# sensor.net
KiCad netlist of a schematic drawn in Altium Designer
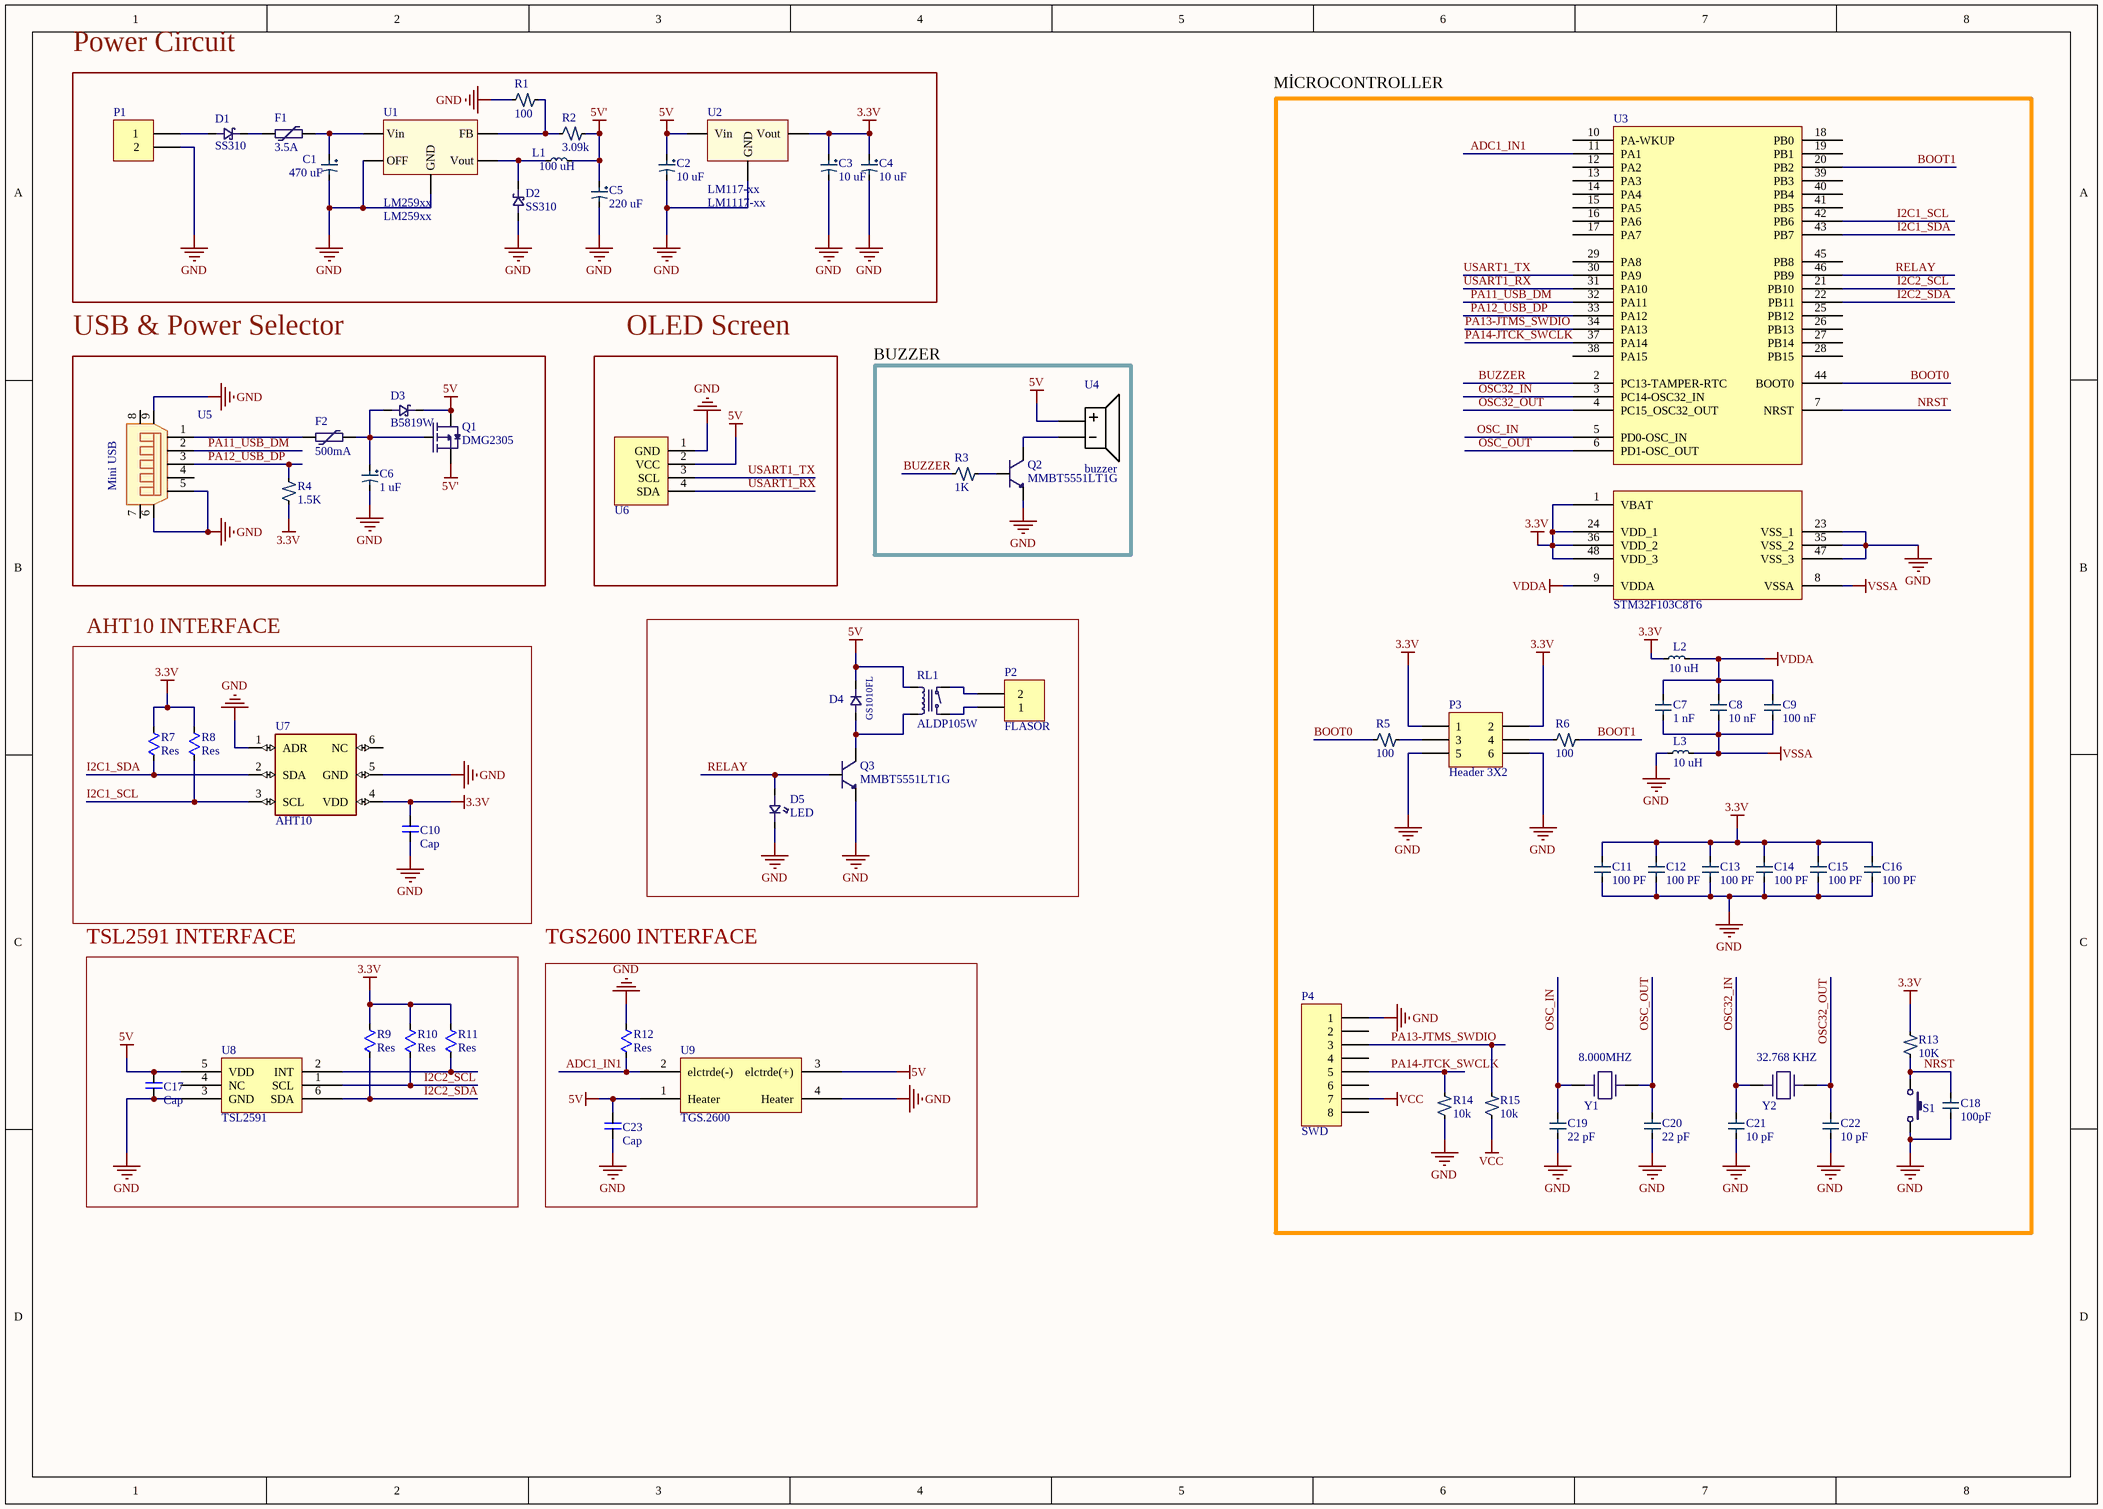
[diagram p0: sensor.SchDoc]

(export (version "E")
  (design (tool "Eeschema 10.0.6"))
  (components
    (comp (ref "C1")
      (value "470 uF")
      (footprint "10X10.5 Cap")
      (description "Cap Pole")
      (libsource (lib "Passive Comp") (part "Capasitor Pole"))
    )
    (comp (ref "C2")
      (value "10 uF")
      (footprint "Case A")
      (description "Cap Pole")
      (libsource (lib "Passive Comp") (part "Capasitor Pole"))
    )
    (comp (ref "C3")
      (value "10 uF")
      (footprint "Case A")
      (description "Cap Pole")
      (libsource (lib "Passive Comp") (part "Capasitor Pole"))
    )
    (comp (ref "C4")
      (value "10 uF")
      (footprint "Case A")
      (description "Cap Pole")
      (libsource (lib "Passive Comp") (part "Capasitor Pole"))
    )
    (comp (ref "C5")
      (value "220 uF")
      (footprint "10X10.5 Cap")
      (description "Cap Pole")
      (libsource (lib "Passive Comp") (part "Capasitor Pole"))
    )
    (comp (ref "C6")
      (value "1 uF")
      (footprint "Case A")
      (description "Cap Pole")
      (libsource (lib "Passive Comp") (part "Capasitor Pole"))
    )
    (comp (ref "C7")
      (value "1 nF")
      (footprint "0603 CAP")
      (description "Cap SMD")
      (libsource (lib "Passive Comp") (part "Capasitor"))
    )
    (comp (ref "C8")
      (value "10 nF")
      (footprint "0603 CAP")
      (description "Cap SMD")
      (libsource (lib "Passive Comp") (part "Capasitor"))
    )
    (comp (ref "C9")
      (value "100 nF")
      (footprint "0603 CAP")
      (description "Cap SMD")
      (libsource (lib "Passive Comp") (part "Capasitor"))
    )
    (comp (ref "C10")
      (value "Cap")
      (footprint "0805 Cap")
      (description "Cap Small")
      (libsource (lib "Passive Comp.") (part "Cap"))
    )
    (comp (ref "C11")
      (value "100 PF")
      (footprint "0603 CAP")
      (description "Cap SMD")
      (libsource (lib "Passive Comp") (part "Capasitor"))
    )
    (comp (ref "C12")
      (value "100 PF")
      (footprint "0603 CAP")
      (description "Cap SMD")
      (libsource (lib "Passive Comp") (part "Capasitor"))
    )
    (comp (ref "C13")
      (value "100 PF")
      (footprint "0603 CAP")
      (description "Cap SMD")
      (libsource (lib "Passive Comp") (part "Capasitor"))
    )
    (comp (ref "C14")
      (value "100 PF")
      (footprint "0603 CAP")
      (description "Cap SMD")
      (libsource (lib "Passive Comp") (part "Capasitor"))
    )
    (comp (ref "C15")
      (value "100 PF")
      (footprint "0603 CAP")
      (description "Cap SMD")
      (libsource (lib "Passive Comp") (part "Capasitor"))
    )
    (comp (ref "C16")
      (value "100 PF")
      (footprint "0603 CAP")
      (description "Cap SMD")
      (libsource (lib "Passive Comp") (part "Capasitor"))
    )
    (comp (ref "C17")
      (value "Cap")
      (footprint "0603 CAP")
      (description "Cap Small")
      (libsource (lib "Passive Comp.") (part "Cap"))
    )
    (comp (ref "C18")
      (value "100pF")
      (footprint "0603 CAP")
      (description "Cap SMD")
      (libsource (lib "Passive Comp") (part "Capasitor"))
    )
    (comp (ref "C19")
      (value "22 pF")
      (footprint "0603 CAP")
      (description "Cap SMD")
      (libsource (lib "Passive Comp") (part "Capasitor"))
    )
    (comp (ref "C20")
      (value "22 pF")
      (footprint "0603 CAP")
      (description "Cap SMD")
      (libsource (lib "Passive Comp") (part "Capasitor"))
    )
    (comp (ref "C21")
      (value "10 pF")
      (footprint "0603 CAP")
      (description "Cap SMD")
      (libsource (lib "Passive Comp") (part "Capasitor"))
    )
    (comp (ref "C22")
      (value "10 pF")
      (footprint "0603 CAP")
      (description "Cap SMD")
      (libsource (lib "Passive Comp") (part "Capasitor"))
    )
    (comp (ref "C23")
      (value "Cap")
      (footprint "0603 CAP")
      (description "Cap Small")
      (libsource (lib "Passive Comp.") (part "Cap"))
    )
    (comp (ref "D1")
      (value "SS310")
      (footprint "DO-214AA")
      (description "DIODE SCHOTTKY 3A 100V DO-214AA SMB HOTTECH")
      (libsource (lib "Diyot") (part "SS310-DO214AA-HT"))
    )
    (comp (ref "D2")
      (value "SS310")
      (footprint "DO-214AA")
      (description "DIODE SCHOTTKY 3A 100V DO-214AA SMB HOTTECH")
      (libsource (lib "Diyot") (part "SS310-DO214AA-HT"))
    )
    (comp (ref "D3")
      (value "B5819W")
      (footprint "SOD123")
      (description "DIODE SCHOTTKY 1A 40V SOD123")
      (libsource (lib "Diyot") (part "B5819W"))
    )
    (comp (ref "D4")
      (value "GS1010FL")
      (footprint "SOD123FL")
      (description "DIODE STAND. Single 1A 1000V SMT SOD123FL")
      (libsource (lib "Diyot") (part "GS1010FL_R1_00001"))
    )
    (comp (ref "D5") (value "LED") (footprint "0603 Led") (libsource (lib "Diyot") (part "LED")))
    (comp (ref "F1")
      (value "3.5A")
      (footprint "6125 Fuse")
      (description "25H0500G 125V 500mA 6125 SMD Sigorta")
      (libsource (lib "Fuse") (part "SMD Fuse"))
    )
    (comp (ref "F2")
      (value "500mA")
      (footprint "6125 Fuse")
      (description "25H0500G 125V 500mA 6125 SMD Sigorta")
      (libsource (lib "Fuse") (part "SMD Fuse"))
    )
    (comp (ref "L1")
      (value "100 uH")
      (footprint "12X12X5MM INDUCTOR")
      (description "IND SMD")
      (libsource (lib "Passive Comp") (part "Inductor"))
    )
    (comp (ref "L2")
      (value "10 uH")
      (footprint "0603 IND")
      (description "IND SMD")
      (libsource (lib "Passive Comp") (part "Inductor"))
    )
    (comp (ref "L3")
      (value "10 uH")
      (footprint "0603 IND")
      (description "IND SMD")
      (libsource (lib "Passive Comp") (part "Inductor"))
    )
    (comp (ref "P1")
      (value "Klemens 5.08")
      (footprint "KLEMENS 5.08MM-2")
      (description "2 Pin 5.08mm 90° Erkek Geçmeli Turuncu Klemens")
      (libsource (lib "Klemens") (part "Klemens 5.08 2 pin"))
    )
    (comp (ref "P2")
      (value "FLASÖR")
      (footprint "KLEMENS 5.08MM-2")
      (description "2 Pin 5.08mm 90° Erkek Geçmeli Turuncu Klemens")
      (libsource (lib "") (part "Klemens 5.08 2 pin_1"))
    )
    (comp (ref "P3")
      (value "Header 3X2")
      (footprint "HDR2X3")
      (description "Header, 3-Pin, Dual row")
      (fields (field (name "PUBLISHER") "Altium Limited"))
      (libsource (lib "Miscellaneous Connectors") (part "Header 3X2"))
    )
    (comp (ref "P4")
      (value "SWD")
      (footprint "2X4 BOX HEADER")
      (description "FEMALE HEADER 2X4 90C")
      (libsource (lib "Header") (part "FEMALE HEADER 2X4 90C"))
    )
    (comp (ref "Q1")
      (value "DMG2305")
      (footprint "SOT23")
      (description "MOSFET DIS.4.2A 20V P-CH SOT23 ENHANCEMENT SMT")
      (libsource (lib "Anahtarlama") (part "DMG2305"))
    )
    (comp (ref "Q2")
      (value "MMBT5551LT1G")
      (footprint "SOT23")
      (description "TRANSISTOR DIS.600mA 160V NPN SOT23 H.VOLT SMT")
      (libsource (lib "Anahtarlama") (part "MMBT5551LT1G"))
    )
    (comp (ref "Q3")
      (value "MMBT5551LT1G")
      (footprint "SOT23")
      (description "TRANSISTOR DIS.600mA 160V NPN SOT23 H.VOLT SMT")
      (libsource (lib "Anahtarlama") (part "MMBT5551LT1G"))
    )
    (comp (ref "R1")
      (value "100")
      (footprint "0603 RES")
      (description "Res SMD")
      (libsource (lib "Passive Comp") (part "Resistor"))
    )
    (comp (ref "R2")
      (value "3.09k")
      (footprint "0603 RES")
      (description "Res SMD")
      (libsource (lib "Passive Comp") (part "Resistor"))
    )
    (comp (ref "R3")
      (value "1K")
      (footprint "0603 RES")
      (description "Res SMD")
      (libsource (lib "") (part "Resistor_1"))
    )
    (comp (ref "R4")
      (value "1.5K")
      (footprint "0603 RES")
      (description "Res SMD")
      (libsource (lib "Passive Comp") (part "Resistor"))
    )
    (comp (ref "R5")
      (value "100")
      (footprint "0603 RES")
      (description "Res SMD")
      (libsource (lib "Passive Comp") (part "Resistor"))
    )
    (comp (ref "R6")
      (value "100")
      (footprint "0603 RES")
      (description "Res SMD")
      (libsource (lib "Passive Comp") (part "Resistor"))
    )
    (comp (ref "R7")
      (value "Res")
      (footprint "0603 RES")
      (description "Res Small")
      (libsource (lib "Passive Comp.") (part "Res"))
    )
    (comp (ref "R8")
      (value "Res")
      (footprint "0603 RES")
      (description "Res Small")
      (libsource (lib "Passive Comp.") (part "Res"))
    )
    (comp (ref "R9")
      (value "Res")
      (footprint "0603 RES")
      (description "Res Small")
      (libsource (lib "Passive Comp.") (part "Res"))
    )
    (comp (ref "R10")
      (value "Res")
      (footprint "0603 RES")
      (description "Res Small")
      (libsource (lib "Passive Comp.") (part "Res"))
    )
    (comp (ref "R11")
      (value "Res")
      (footprint "0603 RES")
      (description "Res Small")
      (libsource (lib "Passive Comp.") (part "Res"))
    )
    (comp (ref "R12")
      (value "Res")
      (footprint "0603 RES")
      (description "Res Small")
      (libsource (lib "Passive Comp.") (part "Res"))
    )
    (comp (ref "R13")
      (value "10K")
      (footprint "0603 RES")
      (description "Res SMD")
      (libsource (lib "Passive Comp") (part "Resistor"))
    )
    (comp (ref "R14")
      (value "10k")
      (footprint "0603 RES")
      (description "Res SMD")
      (libsource (lib "Passive Comp") (part "Resistor"))
    )
    (comp (ref "R15")
      (value "10k")
      (footprint "0603 RES")
      (description "Res SMD")
      (libsource (lib "Passive Comp") (part "Resistor"))
    )
    (comp (ref "RL1")
      (value "ALDP105W")
      (footprint "SPST-NO (1 Form A)")
      (description "RELAY 5A 5V 1a PANASONIC")
      (libsource (lib "Anahtarlama") (part "ALDP105W"))
    )
    (comp (ref "S1")
      (value "Switch")
      (footprint "6x6mm Tach Switch")
      (description "SWITCH TACT 6.00x6.00 4.30mm 250gF SMT V/T")
      (libsource (lib "Switch") (part "Switch Tach V/T"))
    )
    (comp (ref "U1")
      (value "LM259xx")
      (footprint "d2pak-5")
      (description "Voltaga Regulator")
      (fields (field (name "ALTIUM_VALUE") "LM259xx"))
      (libsource (lib "Voltage Reg.") (part "LM259xx"))
    )
    (comp (ref "U2")
      (value "LM117-xx")
      (footprint "SOT223-3")
      (description "Voltaga Regulator")
      (fields (field (name "ALTIUM_VALUE") "LM1117-xx"))
      (libsource (lib "Voltage Reg.") (part "LM117-xx"))
    )
    (comp (ref "U3")
      (value "STM32F103C8T6")
      (footprint "LQFP48")
      (description "IC-32F103C MCU 32BIT 64KB FLASH 48LQFP")
      (libsource (lib "STM") (part "STM32F103C8T6TR"))
    )
    (comp (ref "U4") (value "buzzer") (footprint "BUZZER") (libsource (lib "buzzer") (part "buzzer")))
    (comp (ref "U5")
      (value "Mini USB")
      (footprint "MİNİ USB")
      (description "CONNECTORUSB MINI B TYPE 5PIN SMT R/A FEMALE")
      (libsource (lib "Usb") (part "Mini USB"))
    )
    (comp (ref "U6")
      (value "OLED 128X32")
      (footprint "128x32 OLED")
      (description "128x32 Oled Lcd Ekran 0.91 Inch SSD1306")
      (libsource (lib "Ekran") (part "OLED 128X32"))
    )
    (comp (ref "U7")
      (value "AHT10")
      (footprint "AHT_QFN")
      (description "Temperature and humidity sensor")
      (fields (field (name "MF") "Asair"))
      (libsource (lib "AHT10") (part "AHT10"))
    )
    (comp (ref "U8")
      (value "TSL2591")
      (footprint "SON65P200X200X90-7N")
      (libsource (lib "TSL2591") (part "TSL2591"))
    )
    (comp (ref "U9")
      (value "TGS.2600")
      (footprint "TO180P920H1340-4")
      (libsource (lib "TGS2600") (part "TGS.2600"))
    )
    (comp (ref "Y1")
      (value "8.000MHZ")
      (footprint "SMD-2 XTAL")
      (description "CRYSTAL 8MHZ 18PF 2-SMD ABRACON")
      (libsource (lib "XTAL") (part "8 MHZ XTAL"))
    )
    (comp (ref "Y2")
      (value "32.768 KHZ")
      (footprint "3.20x1.50x0.80")
      (description "CRYSTAL 32.7680kHz 12.5pF 20ppm")
      (libsource (lib "XTAL") (part "32.7680kHz"))
    )
  )
  (nets
    (net (code "2") (name "/ADC1_IN1") (class "Default")
      (node (ref "R12") (pin "1") (pinfunction "1_1") (pintype "passive"))
      (node (ref "U3") (pin "11") (pinfunction "PA1_11") (pintype "passive"))
      (node (ref "U9") (pin "2") (pinfunction "elctrde(-)_2") (pintype "passive"))
    )
    (net (code "3") (name "/BOOT0") (class "Default")
      (node (ref "R5") (pin "1") (pinfunction "1_1") (pintype "passive"))
      (node (ref "U3") (pin "44") (pinfunction "BOOT0_44") (pintype "passive"))
    )
    (net (code "4") (name "/BOOT1") (class "Default")
      (node (ref "R6") (pin "2") (pinfunction "2_2") (pintype "passive"))
      (node (ref "U3") (pin "20") (pinfunction "PB2_20") (pintype "passive"))
    )
    (net (code "5") (name "/BUZZER") (class "Default")
      (node (ref "R3") (pin "1") (pinfunction "1_1") (pintype "passive"))
      (node (ref "U3") (pin "2") (pinfunction "PC13-TAMPER-RTC_2") (pintype "passive"))
    )
    (net (code "6") (name "/I2C1_SCL") (class "Default")
      (node (ref "R8") (pin "1") (pinfunction "1_1") (pintype "passive"))
      (node (ref "U3") (pin "42") (pinfunction "PB6_42") (pintype "passive"))
      (node (ref "U7") (pin "3") (pinfunction "SCL_3") (pintype "bidirectional"))
    )
    (net (code "7") (name "/I2C1_SDA") (class "Default")
      (node (ref "R7") (pin "1") (pinfunction "1_1") (pintype "passive"))
      (node (ref "U3") (pin "43") (pinfunction "PB7_43") (pintype "passive"))
      (node (ref "U7") (pin "2") (pinfunction "SDA_2") (pintype "bidirectional"))
    )
    (net (code "8") (name "/I2C2_SCL") (class "Default")
      (node (ref "R10") (pin "1") (pinfunction "1_1") (pintype "passive"))
      (node (ref "U3") (pin "21") (pinfunction "PB10_21") (pintype "passive"))
      (node (ref "U8") (pin "1") (pinfunction "SCL_1") (pintype "passive"))
    )
    (net (code "9") (name "/I2C2_SDA") (class "Default")
      (node (ref "R9") (pin "1") (pinfunction "1_1") (pintype "passive"))
      (node (ref "U3") (pin "22") (pinfunction "PB11_22") (pintype "passive"))
      (node (ref "U8") (pin "6") (pinfunction "SDA_6") (pintype "passive"))
    )
    (net (code "10") (name "/NRST") (class "Default")
      (node (ref "C18") (pin "2") (pinfunction "2_2") (pintype "passive"))
      (node (ref "R13") (pin "1") (pinfunction "1_1") (pintype "passive"))
      (node (ref "S1") (pin "1") (pinfunction "1_1") (pintype "passive"))
      (node (ref "U3") (pin "7") (pinfunction "NRST_7") (pintype "passive"))
    )
    (net (code "11") (name "/OSC32_IN") (class "Default")
      (node (ref "C21") (pin "2") (pinfunction "2_2") (pintype "passive"))
      (node (ref "U3") (pin "3") (pinfunction "PC14-OSC32_IN_3") (pintype "passive"))
      (node (ref "Y2") (pin "1") (pinfunction "1_1") (pintype "passive"))
    )
    (net (code "12") (name "/OSC32_OUT") (class "Default")
      (node (ref "C22") (pin "2") (pinfunction "2_2") (pintype "passive"))
      (node (ref "U3") (pin "4") (pinfunction "PC15_OSC32_OUT_4") (pintype "passive"))
      (node (ref "Y2") (pin "2") (pinfunction "2_2") (pintype "passive"))
    )
    (net (code "13") (name "/OSC_IN") (class "Default")
      (node (ref "C19") (pin "2") (pinfunction "2_2") (pintype "passive"))
      (node (ref "U3") (pin "5") (pinfunction "PD0-OSC_IN_5") (pintype "passive"))
      (node (ref "Y1") (pin "1") (pinfunction "1_1") (pintype "passive"))
    )
    (net (code "14") (name "/OSC_OUT") (class "Default")
      (node (ref "C20") (pin "2") (pinfunction "2_2") (pintype "passive"))
      (node (ref "U3") (pin "6") (pinfunction "PD1-OSC_OUT_6") (pintype "passive"))
      (node (ref "Y1") (pin "2") (pinfunction "2_2") (pintype "passive"))
    )
    (net (code "15") (name "/PA11_USB_DM") (class "Default")
      (node (ref "U3") (pin "32") (pinfunction "PA11_32") (pintype "passive"))
      (node (ref "U5") (pin "2") (pinfunction "D-_2") (pintype "passive"))
    )
    (net (code "16") (name "/PA12_USB_DP") (class "Default")
      (node (ref "R4") (pin "2") (pinfunction "2_2") (pintype "passive"))
      (node (ref "U3") (pin "33") (pinfunction "PA12_33") (pintype "passive"))
      (node (ref "U5") (pin "3") (pinfunction "D+_3") (pintype "passive"))
    )
    (net (code "17") (name "/PA13-JTMS_SWDIO") (class "Default")
      (node (ref "P4") (pin "3") (pinfunction "3_3") (pintype "passive"))
      (node (ref "R15") (pin "2") (pinfunction "2_2") (pintype "passive"))
      (node (ref "U3") (pin "34") (pinfunction "PA13_34") (pintype "passive"))
    )
    (net (code "18") (name "/PA14-JTCK_SWCLK") (class "Default")
      (node (ref "P4") (pin "5") (pinfunction "5_5") (pintype "passive"))
      (node (ref "R14") (pin "2") (pinfunction "2_2") (pintype "passive"))
      (node (ref "U3") (pin "37") (pinfunction "PA14_37") (pintype "passive"))
    )
    (net (code "19") (name "/RELAY") (class "Default")
      (node (ref "D5") (pin "1") (pinfunction "Anode_1") (pintype "passive"))
      (node (ref "Q3") (pin "1") (pinfunction "Base_1") (pintype "passive"))
      (node (ref "U3") (pin "46") (pinfunction "PB9_46") (pintype "passive"))
    )
    (net (code "20") (name "/USART1_RX") (class "Default")
      (node (ref "U3") (pin "31") (pinfunction "PA10_31") (pintype "passive"))
      (node (ref "U6") (pin "4") (pinfunction "SDA_4") (pintype "passive"))
    )
    (net (code "21") (name "/USART1_TX") (class "Default")
      (node (ref "U3") (pin "30") (pinfunction "PA9_30") (pintype "passive"))
      (node (ref "U6") (pin "3") (pinfunction "SCL_3") (pintype "passive"))
    )
    (net (code "22") (name "3.3V") (class "Default")
      (node (ref "C10") (pin "1") (pinfunction "1_1") (pintype "passive"))
      (node (ref "C11") (pin "2") (pinfunction "2_2") (pintype "passive"))
      (node (ref "C12") (pin "2") (pinfunction "2_2") (pintype "passive"))
      (node (ref "C13") (pin "2") (pinfunction "2_2") (pintype "passive"))
      (node (ref "C14") (pin "2") (pinfunction "2_2") (pintype "passive"))
      (node (ref "C15") (pin "2") (pinfunction "2_2") (pintype "passive"))
      (node (ref "C16") (pin "2") (pinfunction "2_2") (pintype "passive"))
      (node (ref "C3") (pin "1") (pinfunction "1_1") (pintype "passive"))
      (node (ref "C4") (pin "1") (pinfunction "1_1") (pintype "passive"))
      (node (ref "L2") (pin "1") (pinfunction "1_1") (pintype "passive"))
      (node (ref "P3") (pin "1") (pinfunction "1_1") (pintype "passive"))
      (node (ref "P3") (pin "2") (pinfunction "2_2") (pintype "passive"))
      (node (ref "R10") (pin "2") (pinfunction "2_2") (pintype "passive"))
      (node (ref "R11") (pin "2") (pinfunction "2_2") (pintype "passive"))
      (node (ref "R13") (pin "2") (pinfunction "2_2") (pintype "passive"))
      (node (ref "R4") (pin "1") (pinfunction "1_1") (pintype "passive"))
      (node (ref "R7") (pin "2") (pinfunction "2_2") (pintype "passive"))
      (node (ref "R8") (pin "2") (pinfunction "2_2") (pintype "passive"))
      (node (ref "R9") (pin "2") (pinfunction "2_2") (pintype "passive"))
      (node (ref "U2") (pin "2") (pinfunction "Vout_2") (pintype "passive"))
      (node (ref "U3") (pin "1") (pinfunction "VBAT_1") (pintype "passive"))
      (node (ref "U3") (pin "24") (pinfunction "VDD_1_24") (pintype "passive"))
      (node (ref "U3") (pin "36") (pinfunction "VDD_2_36") (pintype "passive"))
      (node (ref "U3") (pin "48") (pinfunction "VDD_3_48") (pintype "passive"))
      (node (ref "U7") (pin "4") (pinfunction "VDD_4") (pintype "bidirectional"))
    )
    (net (code "23") (name "5V") (class "Default")
      (node (ref "C17") (pin "1") (pinfunction "1_1") (pintype "passive"))
      (node (ref "C2") (pin "1") (pinfunction "1_1") (pintype "passive"))
      (node (ref "C23") (pin "1") (pinfunction "1_1") (pintype "passive"))
      (node (ref "D3") (pin "2") (pinfunction "Cathode_2") (pintype "passive"))
      (node (ref "D4") (pin "2") (pinfunction "Cathode_2") (pintype "passive"))
      (node (ref "Q1") (pin "3") (pinfunction "Drain_3") (pintype "passive"))
      (node (ref "RL1") (pin "1") (pinfunction "Coil1_1") (pintype "passive"))
      (node (ref "U2") (pin "3") (pinfunction "Vin_3") (pintype "passive"))
      (node (ref "U4") (pin "1") (pinfunction "1_1") (pintype "passive"))
      (node (ref "U6") (pin "2") (pinfunction "VCC_2") (pintype "passive"))
      (node (ref "U8") (pin "5") (pinfunction "VDD_5") (pintype "passive"))
      (node (ref "U9") (pin "1") (pinfunction "Heater_1") (pintype "passive"))
      (node (ref "U9") (pin "3") (pinfunction "elctrde(+)_3") (pintype "passive"))
    )
    (net (code "24") (name "5V'") (class "Default")
      (node (ref "C5") (pin "1") (pinfunction "1_1") (pintype "passive"))
      (node (ref "L1") (pin "2") (pinfunction "2_2") (pintype "passive"))
      (node (ref "Q1") (pin "2") (pinfunction "Source_2") (pintype "passive"))
      (node (ref "R2") (pin "2") (pinfunction "2_2") (pintype "passive"))
    )
    (net (code "25") (name "GND") (class "Default")
      (node (ref "C1") (pin "2") (pinfunction "2_2") (pintype "passive"))
      (node (ref "C10") (pin "2") (pinfunction "2_2") (pintype "passive"))
      (node (ref "C11") (pin "1") (pinfunction "1_1") (pintype "passive"))
      (node (ref "C12") (pin "1") (pinfunction "1_1") (pintype "passive"))
      (node (ref "C13") (pin "1") (pinfunction "1_1") (pintype "passive"))
      (node (ref "C14") (pin "1") (pinfunction "1_1") (pintype "passive"))
      (node (ref "C15") (pin "1") (pinfunction "1_1") (pintype "passive"))
      (node (ref "C16") (pin "1") (pinfunction "1_1") (pintype "passive"))
      (node (ref "C17") (pin "2") (pinfunction "2_2") (pintype "passive"))
      (node (ref "C18") (pin "1") (pinfunction "1_1") (pintype "passive"))
      (node (ref "C19") (pin "1") (pinfunction "1_1") (pintype "passive"))
      (node (ref "C2") (pin "2") (pinfunction "2_2") (pintype "passive"))
      (node (ref "C20") (pin "1") (pinfunction "1_1") (pintype "passive"))
      (node (ref "C21") (pin "1") (pinfunction "1_1") (pintype "passive"))
      (node (ref "C22") (pin "1") (pinfunction "1_1") (pintype "passive"))
      (node (ref "C23") (pin "2") (pinfunction "2_2") (pintype "passive"))
      (node (ref "C3") (pin "2") (pinfunction "2_2") (pintype "passive"))
      (node (ref "C4") (pin "2") (pinfunction "2_2") (pintype "passive"))
      (node (ref "C5") (pin "2") (pinfunction "2_2") (pintype "passive"))
      (node (ref "C6") (pin "2") (pinfunction "2_2") (pintype "passive"))
      (node (ref "D2") (pin "1") (pinfunction "Anode_1") (pintype "passive"))
      (node (ref "D5") (pin "2") (pinfunction "Cathode_2") (pintype "passive"))
      (node (ref "L3") (pin "1") (pinfunction "1_1") (pintype "passive"))
      (node (ref "P1") (pin "2") (pinfunction "2_2") (pintype "passive"))
      (node (ref "P3") (pin "5") (pinfunction "5_5") (pintype "passive"))
      (node (ref "P3") (pin "6") (pinfunction "6_6") (pintype "passive"))
      (node (ref "P4") (pin "1") (pinfunction "1_1") (pintype "passive"))
      (node (ref "Q2") (pin "2") (pinfunction "Emitter_2") (pintype "passive"))
      (node (ref "Q3") (pin "2") (pinfunction "Emitter_2") (pintype "passive"))
      (node (ref "R1") (pin "1") (pinfunction "1_1") (pintype "passive"))
      (node (ref "R12") (pin "2") (pinfunction "2_2") (pintype "passive"))
      (node (ref "R14") (pin "1") (pinfunction "1_1") (pintype "passive"))
      (node (ref "S1") (pin "2") (pinfunction "2_2") (pintype "passive"))
      (node (ref "U1") (pin "3") (pinfunction "GND_3") (pintype "passive"))
      (node (ref "U1") (pin "5") (pinfunction "OFF_5") (pintype "passive"))
      (node (ref "U2") (pin "1") (pinfunction "GND_1") (pintype "passive"))
      (node (ref "U3") (pin "23") (pinfunction "VSS_1_23") (pintype "passive"))
      (node (ref "U3") (pin "35") (pinfunction "VSS_2_35") (pintype "passive"))
      (node (ref "U3") (pin "47") (pinfunction "VSS_3_47") (pintype "passive"))
      (node (ref "U5") (pin "5") (pinfunction "GND_5") (pintype "passive"))
      (node (ref "U5") (pin "6") (pinfunction "6_6") (pintype "passive"))
      (node (ref "U5") (pin "9") (pinfunction "9_9") (pintype "passive"))
      (node (ref "U6") (pin "1") (pinfunction "GND_1") (pintype "passive"))
      (node (ref "U7") (pin "1") (pinfunction "ADR_1") (pintype "bidirectional"))
      (node (ref "U7") (pin "5") (pinfunction "GND_5") (pintype "bidirectional"))
      (node (ref "U8") (pin "3") (pinfunction "GND_3") (pintype "passive"))
      (node (ref "U9") (pin "4") (pinfunction "Heater_4") (pintype "passive"))
    )
    (net (code "26") (name "Net-(D1-Anode)") (class "Default")
      (node (ref "D1") (pin "1") (pinfunction "Anode_1") (pintype "passive"))
      (node (ref "P1") (pin "1") (pinfunction "1_1") (pintype "passive"))
    )
    (net (code "27") (name "Net-(D1-Cathode)") (class "Default")
      (node (ref "D1") (pin "2") (pinfunction "Cathode_2") (pintype "passive"))
      (node (ref "F1") (pin "1") (pinfunction "1_1") (pintype "passive"))
    )
    (net (code "28") (name "Net-(D2-Cathode)") (class "Default")
      (node (ref "D2") (pin "2") (pinfunction "Cathode_2") (pintype "passive"))
      (node (ref "L1") (pin "1") (pinfunction "1_1") (pintype "passive"))
      (node (ref "U1") (pin "2") (pinfunction "Vout_2") (pintype "passive"))
    )
    (net (code "29") (name "Net-(D3-Anode)") (class "Default")
      (node (ref "C6") (pin "1") (pinfunction "1_1") (pintype "passive"))
      (node (ref "D3") (pin "1") (pinfunction "Anode_1") (pintype "passive"))
      (node (ref "F2") (pin "2") (pinfunction "2_2") (pintype "passive"))
      (node (ref "Q1") (pin "1") (pinfunction "Gate_1") (pintype "passive"))
    )
    (net (code "30") (name "Net-(D4-Anode)") (class "Default")
      (node (ref "D4") (pin "1") (pinfunction "Anode_1") (pintype "passive"))
      (node (ref "Q3") (pin "3") (pinfunction "Collector_3") (pintype "passive"))
      (node (ref "RL1") (pin "2") (pinfunction "Coil2_2") (pintype "passive"))
    )
    (net (code "31") (name "Net-(P3-Pad3)") (class "Default")
      (node (ref "P3") (pin "3") (pinfunction "3_3") (pintype "passive"))
      (node (ref "R5") (pin "2") (pinfunction "2_2") (pintype "passive"))
    )
    (net (code "32") (name "Net-(P3-Pad4)") (class "Default")
      (node (ref "P3") (pin "4") (pinfunction "4_4") (pintype "passive"))
      (node (ref "R6") (pin "1") (pinfunction "1_1") (pintype "passive"))
    )
    (net (code "33") (name "Net-(Q2-Base)") (class "Default")
      (node (ref "Q2") (pin "1") (pinfunction "Base_1") (pintype "passive"))
      (node (ref "R3") (pin "2") (pinfunction "2_2") (pintype "passive"))
    )
    (net (code "34") (name "Net-(Q2-Collector)") (class "Default")
      (node (ref "Q2") (pin "3") (pinfunction "Collector_3") (pintype "passive"))
      (node (ref "U4") (pin "2") (pinfunction "2_2") (pintype "passive"))
    )
    (net (code "35") (name "Net-(RL1-Com)") (class "Default")
      (node (ref "P2") (pin "2") (pinfunction "2_2") (pintype "passive"))
      (node (ref "RL1") (pin "3") (pinfunction "Com_3") (pintype "passive"))
    )
    (net (code "36") (name "Net-(RL1-NO)") (class "Default")
      (node (ref "P2") (pin "1") (pinfunction "1_1") (pintype "passive"))
      (node (ref "RL1") (pin "4") (pinfunction "NO_4") (pintype "passive"))
    )
    (net (code "37") (name "Net-(U1-FB)") (class "Default")
      (node (ref "R1") (pin "2") (pinfunction "2_2") (pintype "passive"))
      (node (ref "R2") (pin "1") (pinfunction "1_1") (pintype "passive"))
      (node (ref "U1") (pin "4") (pinfunction "FB_4") (pintype "passive"))
    )
    (net (code "38") (name "Net-(U1-Vin)") (class "Default")
      (node (ref "C1") (pin "1") (pinfunction "1_1") (pintype "passive"))
      (node (ref "F1") (pin "2") (pinfunction "2_2") (pintype "passive"))
      (node (ref "U1") (pin "1") (pinfunction "Vin_1") (pintype "passive"))
    )
    (net (code "39") (name "Net-(U5-Vbus)") (class "Default")
      (node (ref "F2") (pin "1") (pinfunction "1_1") (pintype "passive"))
      (node (ref "U5") (pin "1") (pinfunction "Vbus_1") (pintype "passive"))
    )
    (net (code "40") (name "Net-(U8-INT)") (class "Default")
      (node (ref "R11") (pin "1") (pinfunction "1_1") (pintype "passive"))
      (node (ref "U8") (pin "2") (pinfunction "INT_2") (pintype "passive"))
    )
    (net (code "41") (name "VCC") (class "Default")
      (node (ref "P4") (pin "7") (pinfunction "7_7") (pintype "passive"))
      (node (ref "R15") (pin "1") (pinfunction "1_1") (pintype "passive"))
    )
    (net (code "42") (name "VDDA") (class "Default")
      (node (ref "C7") (pin "2") (pinfunction "2_2") (pintype "passive"))
      (node (ref "C8") (pin "2") (pinfunction "2_2") (pintype "passive"))
      (node (ref "C9") (pin "2") (pinfunction "2_2") (pintype "passive"))
      (node (ref "L2") (pin "2") (pinfunction "2_2") (pintype "passive"))
      (node (ref "U3") (pin "9") (pinfunction "VDDA_9") (pintype "passive"))
    )
    (net (code "43") (name "VSSA") (class "Default")
      (node (ref "C7") (pin "1") (pinfunction "1_1") (pintype "passive"))
      (node (ref "C8") (pin "1") (pinfunction "1_1") (pintype "passive"))
      (node (ref "C9") (pin "1") (pinfunction "1_1") (pintype "passive"))
      (node (ref "L3") (pin "2") (pinfunction "2_2") (pintype "passive"))
      (node (ref "U3") (pin "8") (pinfunction "VSSA_8") (pintype "passive"))
    )
    (net (code "44") (name "unconnected-(P4-Pad2)") (class "Default")
      (node (ref "P4") (pin "2") (pinfunction "2_2") (pintype "passive"))
    )
    (net (code "45") (name "unconnected-(P4-Pad4)") (class "Default")
      (node (ref "P4") (pin "4") (pinfunction "4_4") (pintype "passive"))
    )
    (net (code "46") (name "unconnected-(P4-Pad6)") (class "Default")
      (node (ref "P4") (pin "6") (pinfunction "6_6") (pintype "passive"))
    )
    (net (code "47") (name "unconnected-(P4-Pad8)") (class "Default")
      (node (ref "P4") (pin "8") (pinfunction "8_8") (pintype "passive"))
    )
    (net (code "48") (name "unconnected-(U3-PA-WKUP-Pad10)") (class "Default")
      (node (ref "U3") (pin "10") (pinfunction "PA-WKUP_10") (pintype "passive"))
    )
    (net (code "49") (name "unconnected-(U3-PA2-Pad12)") (class "Default")
      (node (ref "U3") (pin "12") (pinfunction "PA2_12") (pintype "passive"))
    )
    (net (code "50") (name "unconnected-(U3-PA3-Pad13)") (class "Default")
      (node (ref "U3") (pin "13") (pinfunction "PA3_13") (pintype "passive"))
    )
    (net (code "51") (name "unconnected-(U3-PA4-Pad14)") (class "Default")
      (node (ref "U3") (pin "14") (pinfunction "PA4_14") (pintype "passive"))
    )
    (net (code "52") (name "unconnected-(U3-PA5-Pad15)") (class "Default")
      (node (ref "U3") (pin "15") (pinfunction "PA5_15") (pintype "passive"))
    )
    (net (code "53") (name "unconnected-(U3-PA6-Pad16)") (class "Default")
      (node (ref "U3") (pin "16") (pinfunction "PA6_16") (pintype "passive"))
    )
    (net (code "54") (name "unconnected-(U3-PA7-Pad17)") (class "Default")
      (node (ref "U3") (pin "17") (pinfunction "PA7_17") (pintype "passive"))
    )
    (net (code "55") (name "unconnected-(U3-PA8-Pad29)") (class "Default")
      (node (ref "U3") (pin "29") (pinfunction "PA8_29") (pintype "passive"))
    )
    (net (code "56") (name "unconnected-(U3-PA15-Pad38)") (class "Default")
      (node (ref "U3") (pin "38") (pinfunction "PA15_38") (pintype "passive"))
    )
    (net (code "57") (name "unconnected-(U3-PB0-Pad18)") (class "Default")
      (node (ref "U3") (pin "18") (pinfunction "PB0_18") (pintype "passive"))
    )
    (net (code "58") (name "unconnected-(U3-PB1-Pad19)") (class "Default")
      (node (ref "U3") (pin "19") (pinfunction "PB1_19") (pintype "passive"))
    )
    (net (code "59") (name "unconnected-(U3-PB3-Pad39)") (class "Default")
      (node (ref "U3") (pin "39") (pinfunction "PB3_39") (pintype "passive"))
    )
    (net (code "60") (name "unconnected-(U3-PB4-Pad40)") (class "Default")
      (node (ref "U3") (pin "40") (pinfunction "PB4_40") (pintype "passive"))
    )
    (net (code "61") (name "unconnected-(U3-PB5-Pad41)") (class "Default")
      (node (ref "U3") (pin "41") (pinfunction "PB5_41") (pintype "passive"))
    )
    (net (code "62") (name "unconnected-(U3-PB8-Pad45)") (class "Default")
      (node (ref "U3") (pin "45") (pinfunction "PB8_45") (pintype "passive"))
    )
    (net (code "63") (name "unconnected-(U3-PB12-Pad25)") (class "Default")
      (node (ref "U3") (pin "25") (pinfunction "PB12_25") (pintype "passive"))
    )
    (net (code "64") (name "unconnected-(U3-PB13-Pad26)") (class "Default")
      (node (ref "U3") (pin "26") (pinfunction "PB13_26") (pintype "passive"))
    )
    (net (code "65") (name "unconnected-(U3-PB14-Pad27)") (class "Default")
      (node (ref "U3") (pin "27") (pinfunction "PB14_27") (pintype "passive"))
    )
    (net (code "66") (name "unconnected-(U3-PB15-Pad28)") (class "Default")
      (node (ref "U3") (pin "28") (pinfunction "PB15_28") (pintype "passive"))
    )
    (net (code "67") (name "unconnected-(U5-IN-Pad4)") (class "Default")
      (node (ref "U5") (pin "4") (pinfunction "IN_4") (pintype "passive"))
    )
    (net (code "68") (name "unconnected-(U5-Pad7)") (class "Default")
      (node (ref "U5") (pin "7") (pinfunction "7_7") (pintype "passive"))
    )
    (net (code "69") (name "unconnected-(U5-Pad8)") (class "Default")
      (node (ref "U5") (pin "8") (pinfunction "8_8") (pintype "passive"))
    )
    (net (code "70") (name "unconnected-(U7-NC-Pad6)") (class "Default")
      (node (ref "U7") (pin "6") (pinfunction "NC_6") (pintype "bidirectional"))
    )
    (net (code "71") (name "unconnected-(U8-NC-Pad4)") (class "Default")
      (node (ref "U8") (pin "4") (pinfunction "NC_4") (pintype "passive"))
    )
  )
)
